# openSX70_ALADDIN_V398C-SEEED_20180222.net
KiCad netlist of a schematic drawn in EAGLE
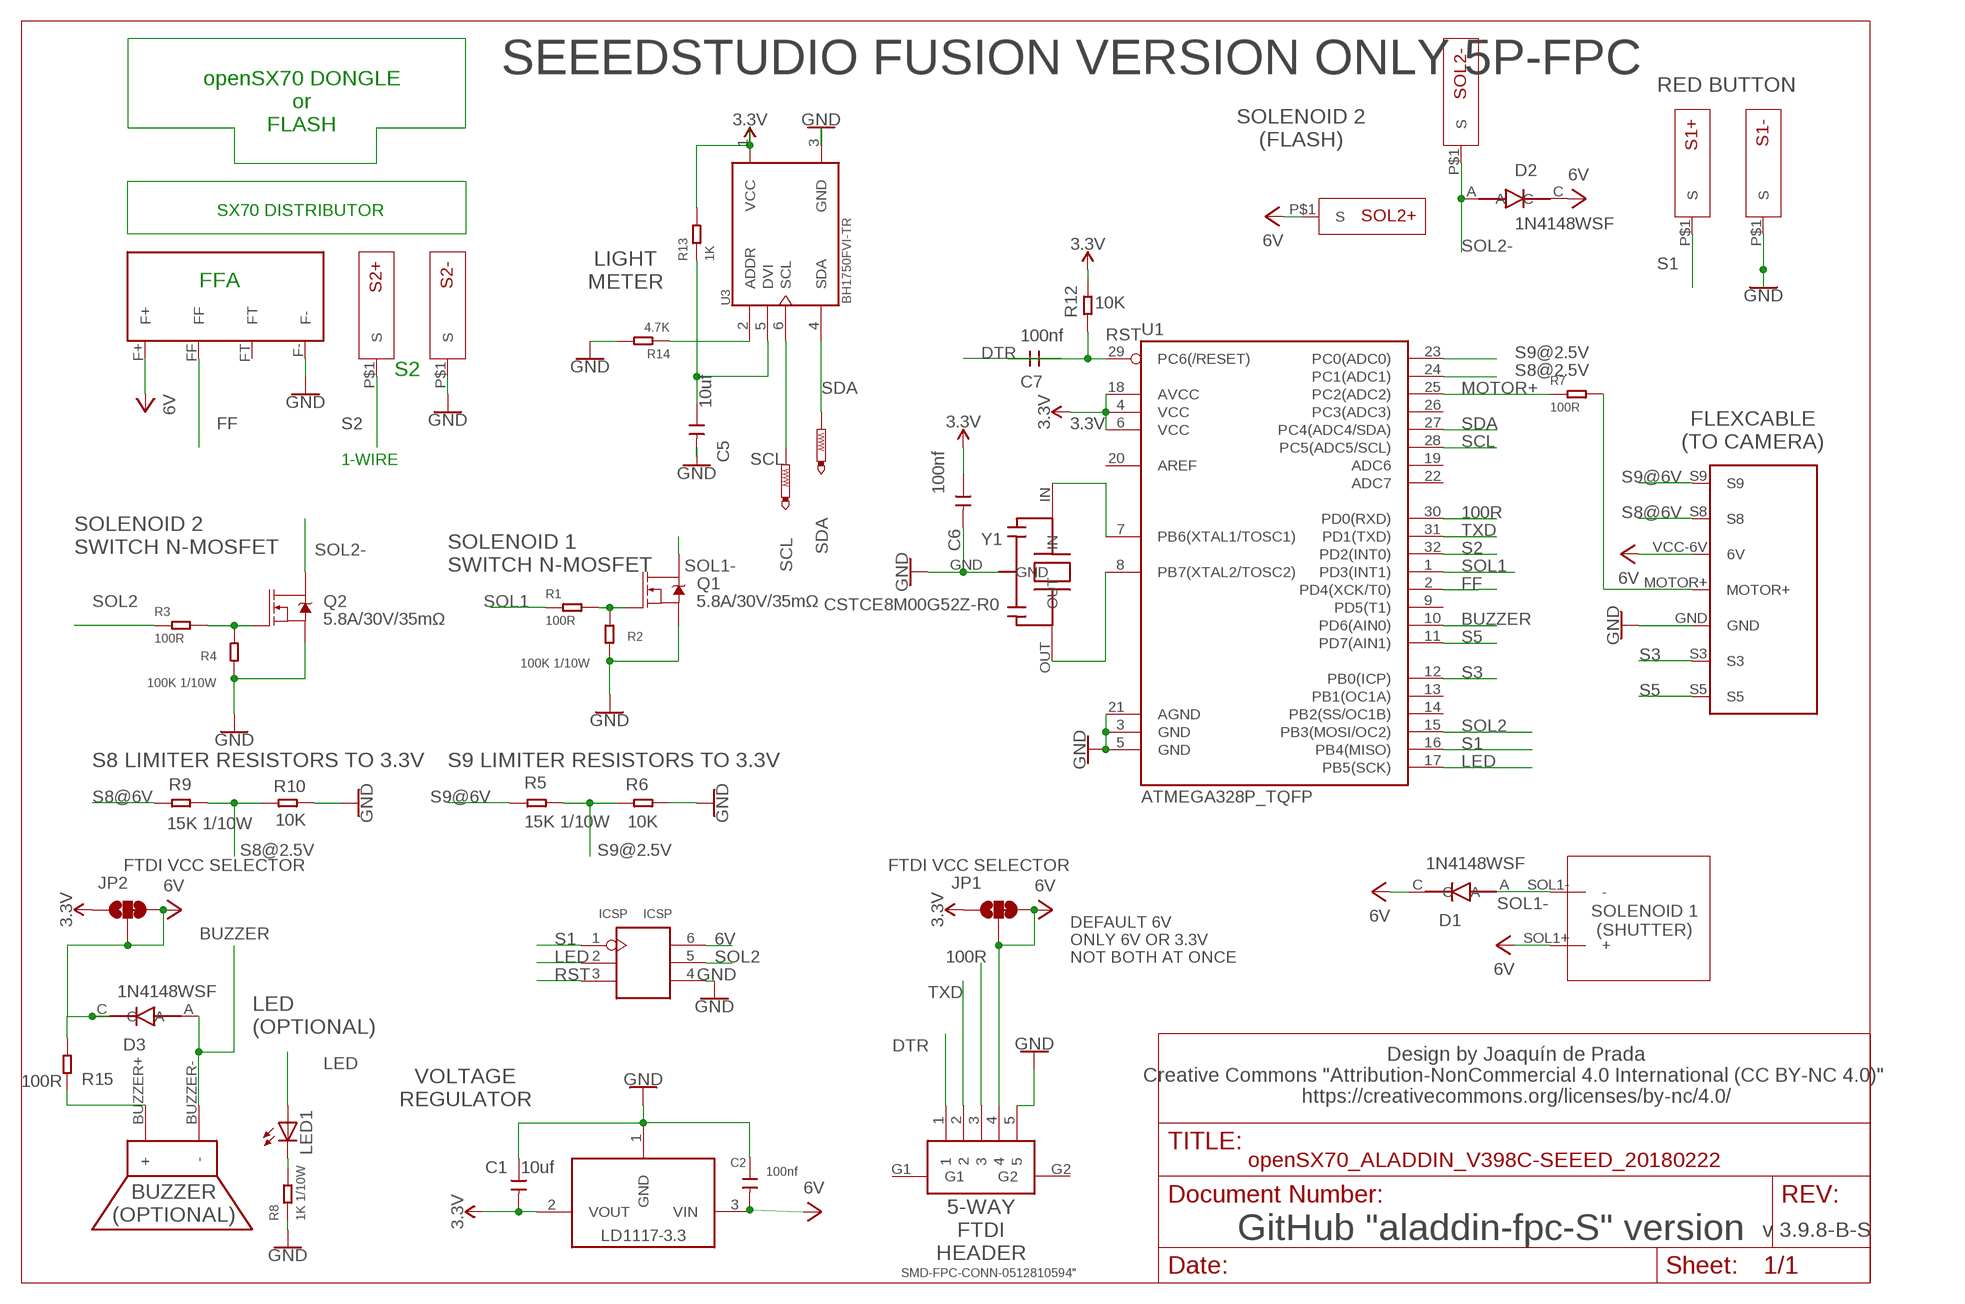
[diagram p0: schematic, sheet 1]

(export (version "E")
  (design (tool "Eeschema 10.0.6"))
  (components
    (comp (ref "C1")
      (value "10uf")
      (footprint "eagle-import:C0603")
      (fields (field (name "MPN") "CC0603KRX5R6BB106"))
      (libsource (lib "eagle-import") (part "CERAMIC-10UF-10V-10%-X5R(0603)"))
    )
    (comp (ref "C2")
      (value "100nf")
      (footprint "eagle-import:C0603")
      (fields (field (name "MPN") "CC0603KRX7R9BB104"))
      (libsource (lib "eagle-import") (part "CERAMIC-100NF-50V-10%-X7R(0603)"))
    )
    (comp (ref "C5")
      (value "10uf")
      (footprint "eagle-import:C0603")
      (fields (field (name "MPN") "CC0603KRX5R6BB106"))
      (libsource (lib "eagle-import") (part "CERAMIC-10UF-10V-10%-X5R(0603)"))
    )
    (comp (ref "C6")
      (value "100nf")
      (footprint "eagle-import:C0603")
      (fields (field (name "MPN") "CC0603KRX7R9BB104"))
      (libsource (lib "eagle-import") (part "CERAMIC-100NF-50V-10%-X7R(0603)"))
    )
    (comp (ref "C7")
      (value "100nf")
      (footprint "eagle-import:C0603")
      (fields (field (name "MPN") "CC0603KRX7R9BB104"))
      (libsource (lib "eagle-import") (part "CERAMIC-100NF-50V-10%-X7R(0603)"))
    )
    (comp (ref "D1")
      (value "1N4148WSF")
      (footprint "eagle-import:SODFL2512X100N")
      (fields (field (name "MANUFACTURER") "Fairchild Semiconductor"))
      (libsource (lib "eagle-import") (part "1N4148WS"))
    )
    (comp (ref "D2")
      (value "1N4148WSF")
      (footprint "eagle-import:SODFL2512X100N")
      (fields (field (name "MANUFACTURER") "Fairchild Semiconductor"))
      (libsource (lib "eagle-import") (part "1N4148WS"))
    )
    (comp (ref "D3")
      (value "1N4148WSF")
      (footprint "eagle-import:SODFL2512X100N")
      (fields (field (name "MANUFACTURER") "Fairchild Semiconductor"))
      (libsource (lib "eagle-import") (part "1N4148WS"))
    )
    (comp (ref "ICSP")
      (value "ICSP")
      (footprint "eagle-import:H2X3-2.54")
      (libsource (lib "eagle-import") (part "ICSP"))
    )
    (comp (ref "JP1")
      (value "FTDI VCC SELECTOR")
      (footprint "eagle-import:SMT-JUMPER_3_1-NC_TRACE_SILK")
      (libsource (lib "eagle-import") (part "JUMPER-SMT_3_1-NC_TRACE_SILK"))
    )
    (comp (ref "JP2")
      (value "FTDI VCC SELECTOR")
      (footprint "eagle-import:SMT-JUMPER_3_1-NC_TRACE_SILK")
      (libsource (lib "eagle-import") (part "JUMPER-SMT_3_1-NC_TRACE_SILK"))
    )
    (comp (ref "LD11172.5V")
      (value "LD1117 2.5V")
      (footprint "eagle-import:SOT223")
      (fields (field (name "MF") "Advanced Monolithic Systems") (field (name "MP") "AMS1117-5.0"))
      (libsource (lib "eagle-import") (part "LD1117-3.3"))
    )
    (comp (ref "LED1")
      (value "LEDCHIPLED_0805")
      (footprint "eagle-import:CHIPLED_0805")
      (libsource (lib "eagle-import") (part "LEDCHIPLED_0805"))
    )
    (comp (ref "Q1")
      (value "5.8A/30V/35mΩ")
      (footprint "eagle-import:SOT23-3")
      (libsource (lib "eagle-import") (part "MOSFET-NCH-AO3404A"))
    )
    (comp (ref "Q2")
      (value "5.8A/30V/35mΩ")
      (footprint "eagle-import:SOT23-3")
      (libsource (lib "eagle-import") (part "MOSFET-NCH-AO3404A"))
    )
    (comp (ref "R1")
      (value "100R")
      (footprint "eagle-import:R0603")
      (fields (field (name "MPN") "RC0603JR-07100RL"))
      (libsource (lib "eagle-import") (part "SMD-RES-100R-5%-1/10W(0603)"))
    )
    (comp (ref "R2")
      (value "100K 1/10W")
      (footprint "eagle-import:R0603")
      (fields (field (name "MPN") "RC0603JR-07100KL"))
      (libsource (lib "eagle-import") (part "SMD-RES-100K-5%-1/10W(0603)"))
    )
    (comp (ref "R3")
      (value "100R")
      (footprint "eagle-import:R0603")
      (fields (field (name "MPN") "RC0603JR-07100RL"))
      (libsource (lib "eagle-import") (part "SMD-RES-100R-5%-1/10W(0603)"))
    )
    (comp (ref "R4")
      (value "100K 1/10W")
      (footprint "eagle-import:R0603")
      (fields (field (name "MPN") "RC0603JR-07100KL"))
      (libsource (lib "eagle-import") (part "SMD-RES-100K-5%-1/10W(0603)"))
    )
    (comp (ref "R5")
      (value "15K 1/10W")
      (footprint "eagle-import:R0603")
      (fields (field (name "MPN") "RC0603FR-0715KL"))
      (libsource (lib "eagle-import") (part "SMD-RES-15K-1%-1/10W(0603)"))
    )
    (comp (ref "R6")
      (value "10K")
      (footprint "eagle-import:R0603")
      (fields (field (name "MPN") "RC0603FR-0710KL"))
      (libsource (lib "eagle-import") (part "SMD-RES-10K-1%-1/10W(0603)"))
    )
    (comp (ref "R7")
      (value "100R")
      (footprint "eagle-import:R0603")
      (fields (field (name "MPN") "RC0603JR-07100RL"))
      (libsource (lib "eagle-import") (part "SMD-RES-100R-5%-1/10W(0603)"))
    )
    (comp (ref "R8")
      (value "1K 1/10W")
      (footprint "eagle-import:R0603")
      (fields (field (name "MPN") "RC0603JR-071KL"))
      (libsource (lib "eagle-import") (part "SMD-RES-1K-5%-1/10W(0603)"))
    )
    (comp (ref "R9")
      (value "15K 1/10W")
      (footprint "eagle-import:R0603")
      (fields (field (name "MPN") "RC0603FR-0715KL"))
      (libsource (lib "eagle-import") (part "SMD-RES-15K-1%-1/10W(0603)"))
    )
    (comp (ref "R10")
      (value "10K")
      (footprint "eagle-import:R0603")
      (fields (field (name "MPN") "RC0603FR-0710KL"))
      (libsource (lib "eagle-import") (part "SMD-RES-10K-1%-1/10W(0603)"))
    )
    (comp (ref "R12")
      (value "10K")
      (footprint "eagle-import:R0603")
      (fields (field (name "MPN") "RC0603FR-0710KL"))
      (libsource (lib "eagle-import") (part "SMD-RES-10K-1%-1/10W(0603)"))
    )
    (comp (ref "R13")
      (value "1K")
      (footprint "eagle-import:R0603")
      (fields (field (name "MPN") "RC0603FR-071KL"))
      (libsource (lib "eagle-import") (part "SMD-RES-1K-1%-1/10W(0603)"))
    )
    (comp (ref "R14")
      (value "4.7K")
      (footprint "eagle-import:R0603")
      (fields (field (name "MPN") "RC0603JR-074K7L"))
      (libsource (lib "eagle-import") (part "SMD-RES-4.7K-5%-1/10W(0603)"))
    )
    (comp (ref "R15")
      (value "100R")
      (footprint "eagle-import:R0603")
      (fields (field (name "MPN") "RC0603JR-07100RL"))
      (libsource (lib "eagle-import") (part "SMD-RES-100R-5%-1/10W(0603)"))
    )
    (comp (ref "S1+")
      (value "SX70-S-PAD-NEW")
      (footprint "eagle-import:SX70-S-PAD2")
      (libsource (lib "eagle-import") (part "SX70-S-PAD-NEW"))
    )
    (comp (ref "S1-")
      (value "SX70-S-PAD-NEW")
      (footprint "eagle-import:SX70-S-PAD2")
      (libsource (lib "eagle-import") (part "SX70-S-PAD-NEW"))
    )
    (comp (ref "S2+")
      (value "SX70-S-PAD-NEW")
      (footprint "eagle-import:SX70-S-PAD2")
      (libsource (lib "eagle-import") (part "SX70-S-PAD-NEW"))
    )
    (comp (ref "S2-")
      (value "SX70-S-PAD-NEW")
      (footprint "eagle-import:SX70-S-PAD2")
      (libsource (lib "eagle-import") (part "SX70-S-PAD-NEW"))
    )
    (comp (ref "SCL")
      (value "PTR1TP08R")
      (footprint "eagle-import:TP08R")
      (libsource (lib "eagle-import") (part "PTR1TP08R"))
    )
    (comp (ref "SDA")
      (value "PTR1TP08R")
      (footprint "eagle-import:TP08R")
      (libsource (lib "eagle-import") (part "PTR1TP08R"))
    )
    (comp (ref "SOL1")
      (value "SX70-SOLENOID1-2PADS")
      (footprint "eagle-import:SX70-SOLENOID1-2")
      (libsource (lib "eagle-import") (part "SX70-SOLENOID1-2PADS"))
    )
    (comp (ref "SOL2+")
      (value "SX70-S-PAD-NEW")
      (footprint "eagle-import:SX70-S-PAD2")
      (libsource (lib "eagle-import") (part "SX70-S-PAD-NEW"))
    )
    (comp (ref "SOL2-")
      (value "SX70-S-PAD-NEW")
      (footprint "eagle-import:SX70-S-PAD2")
      (libsource (lib "eagle-import") (part "SX70-S-PAD-NEW"))
    )
    (comp (ref "U$1")
      (value "SX70-7-PAD")
      (footprint "eagle-import:SX70-7-PAD")
      (libsource (lib "eagle-import") (part "SX70-7-PAD"))
    )
    (comp (ref "U$2")
      (value "FFA")
      (footprint "eagle-import:FFA-PAD-PACKAGE")
      (libsource (lib "eagle-import") (part "SX70-FFA-PAD"))
    )
    (comp (ref "U$3")
      (value "CSET8-5G_V2")
      (footprint "eagle-import:CSET8-5G_PACKAGE")
      (libsource (lib "eagle-import") (part "CSET8-5G_V2"))
    )
    (comp (ref "U$4")
      (value "SMD-FPC-CONN-0512810594\"")
      (footprint "eagle-import:51281-0594")
      (libsource (lib "eagle-import") (part "SMD-FPC-CONN-0512810594{dblquote}"))
    )
    (comp (ref "U1")
      (value "ATMEGA328P_TQFP")
      (footprint "eagle-import:TQFP32-08")
      (libsource (lib "eagle-import") (part "ATMEGA328P_TQFP"))
    )
    (comp (ref "U3")
      (value "BH1750FVI-TR")
      (footprint "eagle-import:SOTFL50P300X75-6N")
      (fields (field (name "MF") "Rohm"))
      (libsource (lib "eagle-import") (part "BH1750FVI-TR"))
    )
    (comp (ref "Y1")
      (value "CSTCE8M00G52Z-R0")
      (footprint "eagle-import:CFP95P160X100-3N")
      (fields (field (name "MF") "Murata") (field (name "MP") "CSTCE16M0V53-R0"))
      (libsource (lib "eagle-import") (part "CSTCE16M0V53-R0"))
    )
  )
  (nets
    (net (code "1") (name "/100R") (class "Default")
      (node (ref "U$4") (pin "3") (pinfunction "3_3") (pintype "bidirectional"))
      (node (ref "U1") (pin "30") (pinfunction "PD0(RXD)_30") (pintype "bidirectional"))
    )
    (net (code "2") (name "/BUZZER") (class "Default")
      (node (ref "D3") (pin "A") (pinfunction "A_A") (pintype "passive"))
      (node (ref "U$3") (pin "BUZZER-") (pinfunction "-_BUZZER-") (pintype "bidirectional"))
      (node (ref "U1") (pin "10") (pinfunction "PD6(AIN0)_10") (pintype "bidirectional"))
    )
    (net (code "3") (name "/DTR") (class "Default")
      (node (ref "C7") (pin "1") (pinfunction "1_1") (pintype "passive"))
      (node (ref "U$4") (pin "1") (pinfunction "1_1") (pintype "bidirectional"))
    )
    (net (code "4") (name "/FF") (class "Default")
      (node (ref "U$2") (pin "FF") (pinfunction "FF_FF") (pintype "bidirectional"))
      (node (ref "U1") (pin "2") (pinfunction "PD4(XCK/T0)_2") (pintype "bidirectional"))
    )
    (net (code "5") (name "/LED") (class "Default")
      (node (ref "ICSP") (pin "2") (pinfunction "SCK_2") (pintype "bidirectional"))
      (node (ref "LED1") (pin "A") (pinfunction "A_A") (pintype "passive"))
      (node (ref "U1") (pin "17") (pinfunction "PB5(SCK)_17") (pintype "bidirectional"))
    )
    (net (code "6") (name "/MOTOR+") (class "Default")
      (node (ref "R7") (pin "1") (pinfunction "1_1") (pintype "passive"))
      (node (ref "U1") (pin "25") (pinfunction "PC2(ADC2)_25") (pintype "bidirectional"))
    )
    (net (code "7") (name "/RST") (class "Default")
      (node (ref "C7") (pin "2") (pinfunction "2_2") (pintype "passive"))
      (node (ref "ICSP") (pin "3") (pinfunction "RST_3") (pintype "bidirectional"))
      (node (ref "R12") (pin "1") (pinfunction "1_1") (pintype "passive"))
      (node (ref "U1") (pin "29") (pinfunction "PC6(/RESET)_29") (pintype "bidirectional"))
    )
    (net (code "8") (name "/S1") (class "Default")
      (node (ref "ICSP") (pin "1") (pinfunction "MISO_1") (pintype "bidirectional"))
      (node (ref "S1+") (pin "P$1") (pinfunction "S_P$1") (pintype "bidirectional"))
      (node (ref "U1") (pin "16") (pinfunction "PB4(MISO)_16") (pintype "bidirectional"))
    )
    (net (code "9") (name "/S2") (class "Default")
      (node (ref "S2+") (pin "P$1") (pinfunction "S_P$1") (pintype "bidirectional"))
      (node (ref "U1") (pin "32") (pinfunction "PD2(INT0)_32") (pintype "bidirectional"))
    )
    (net (code "10") (name "/S3") (class "Default")
      (node (ref "U$1") (pin "S3") (pinfunction "S3_S3") (pintype "bidirectional"))
      (node (ref "U1") (pin "12") (pinfunction "PB0(ICP)_12") (pintype "bidirectional"))
    )
    (net (code "11") (name "/S5") (class "Default")
      (node (ref "U$1") (pin "S5") (pinfunction "S5_S5") (pintype "bidirectional"))
      (node (ref "U1") (pin "11") (pinfunction "PD7(AIN1)_11") (pintype "bidirectional"))
    )
    (net (code "12") (name "/S8@2.5V") (class "Default")
      (node (ref "R10") (pin "1") (pinfunction "1_1") (pintype "passive"))
      (node (ref "R9") (pin "2") (pinfunction "2_2") (pintype "passive"))
      (node (ref "U1") (pin "24") (pinfunction "PC1(ADC1)_24") (pintype "bidirectional"))
    )
    (net (code "13") (name "/S8@6V") (class "Default")
      (node (ref "R9") (pin "1") (pinfunction "1_1") (pintype "passive"))
      (node (ref "U$1") (pin "S8") (pinfunction "S8_S8") (pintype "bidirectional"))
    )
    (net (code "14") (name "/S9@2.5V") (class "Default")
      (node (ref "R5") (pin "2") (pinfunction "2_2") (pintype "passive"))
      (node (ref "R6") (pin "1") (pinfunction "1_1") (pintype "passive"))
      (node (ref "U1") (pin "23") (pinfunction "PC0(ADC0)_23") (pintype "bidirectional"))
    )
    (net (code "15") (name "/S9@6V") (class "Default")
      (node (ref "R5") (pin "1") (pinfunction "1_1") (pintype "passive"))
      (node (ref "U$1") (pin "S9") (pinfunction "S9_S9") (pintype "bidirectional"))
    )
    (net (code "16") (name "/SCL") (class "Default")
      (node (ref "SCL") (pin "TP") (pinfunction "TP_TP") (pintype "input"))
      (node (ref "U1") (pin "28") (pinfunction "PC5(ADC5/SCL)_28") (pintype "bidirectional"))
      (node (ref "U3") (pin "6") (pinfunction "SCL_6") (pintype "input"))
    )
    (net (code "17") (name "/SDA") (class "Default")
      (node (ref "SDA") (pin "TP") (pinfunction "TP_TP") (pintype "input"))
      (node (ref "U1") (pin "27") (pinfunction "PC4(ADC4/SDA)_27") (pintype "bidirectional"))
      (node (ref "U3") (pin "4") (pinfunction "SDA_4") (pintype "bidirectional"))
    )
    (net (code "18") (name "/SOL1") (class "Default")
      (node (ref "R1") (pin "1") (pinfunction "1_1") (pintype "passive"))
      (node (ref "U1") (pin "1") (pinfunction "PD3(INT1)_1") (pintype "bidirectional"))
    )
    (net (code "19") (name "/SOL1-") (class "Default")
      (node (ref "D1") (pin "A") (pinfunction "A_A") (pintype "passive"))
      (node (ref "Q1") (pin "3") (pinfunction "D_3") (pintype "bidirectional"))
      (node (ref "SOL1") (pin "SOL1-") (pinfunction "-_SOL1-") (pintype "bidirectional"))
    )
    (net (code "20") (name "/SOL2") (class "Default")
      (node (ref "ICSP") (pin "5") (pinfunction "MOSI_5") (pintype "bidirectional"))
      (node (ref "R3") (pin "1") (pinfunction "1_1") (pintype "passive"))
      (node (ref "U1") (pin "15") (pinfunction "PB3(MOSI/OC2)_15") (pintype "bidirectional"))
    )
    (net (code "21") (name "/SOL2-") (class "Default")
      (node (ref "D2") (pin "A") (pinfunction "A_A") (pintype "passive"))
      (node (ref "Q2") (pin "3") (pinfunction "D_3") (pintype "bidirectional"))
      (node (ref "SOL2-") (pin "P$1") (pinfunction "S_P$1") (pintype "bidirectional"))
    )
    (net (code "22") (name "/TXD") (class "Default")
      (node (ref "U$4") (pin "2") (pinfunction "2_2") (pintype "bidirectional"))
      (node (ref "U1") (pin "31") (pinfunction "PD1(TXD)_31") (pintype "bidirectional"))
    )
    (net (code "23") (name "3.3V") (class "Default")
      (node (ref "C1") (pin "2") (pinfunction "2_2") (pintype "passive"))
      (node (ref "C6") (pin "1") (pinfunction "1_1") (pintype "passive"))
      (node (ref "JP1") (pin "1") (pinfunction "1_1") (pintype "passive"))
      (node (ref "JP2") (pin "1") (pinfunction "1_1") (pintype "passive"))
      (node (ref "LD11172.5V") (pin "2") (pinfunction "VOUT_2") (pintype "bidirectional"))
      (node (ref "R12") (pin "2") (pinfunction "2_2") (pintype "passive"))
      (node (ref "R13") (pin "2") (pinfunction "2_2") (pintype "passive"))
      (node (ref "U1") (pin "18") (pinfunction "AVCC_18") (pintype "bidirectional"))
      (node (ref "U1") (pin "4") (pinfunction "VCC_4") (pintype "bidirectional"))
      (node (ref "U1") (pin "6") (pinfunction "VCC_6") (pintype "bidirectional"))
      (node (ref "U3") (pin "1") (pinfunction "VCC_1") (pintype "power_in"))
    )
    (net (code "24") (name "6V") (class "Default")
      (node (ref "C2") (pin "2") (pinfunction "2_2") (pintype "passive"))
      (node (ref "D1") (pin "C") (pinfunction "C_C") (pintype "passive"))
      (node (ref "D2") (pin "C") (pinfunction "C_C") (pintype "passive"))
      (node (ref "D3") (pin "C") (pinfunction "C_C") (pintype "passive"))
      (node (ref "ICSP") (pin "6") (pinfunction "VCC_6") (pintype "bidirectional"))
      (node (ref "JP1") (pin "2") (pinfunction "2_2") (pintype "passive"))
      (node (ref "JP1") (pin "3") (pinfunction "3_3") (pintype "passive"))
      (node (ref "JP2") (pin "2") (pinfunction "2_2") (pintype "passive"))
      (node (ref "JP2") (pin "3") (pinfunction "3_3") (pintype "passive"))
      (node (ref "LD11172.5V") (pin "3") (pinfunction "VIN_3") (pintype "bidirectional"))
      (node (ref "R15") (pin "2") (pinfunction "2_2") (pintype "passive"))
      (node (ref "SOL1") (pin "SOL1+") (pinfunction "+_SOL1+") (pintype "bidirectional"))
      (node (ref "SOL2+") (pin "P$1") (pinfunction "S_P$1") (pintype "bidirectional"))
      (node (ref "U$1") (pin "VCC-6V") (pinfunction "6V_VCC-6V") (pintype "bidirectional"))
      (node (ref "U$2") (pin "F+") (pinfunction "F+_F+") (pintype "bidirectional"))
      (node (ref "U$4") (pin "4") (pinfunction "4_4") (pintype "bidirectional"))
    )
    (net (code "25") (name "GND") (class "Default")
      (node (ref "C1") (pin "1") (pinfunction "1_1") (pintype "passive"))
      (node (ref "C2") (pin "1") (pinfunction "1_1") (pintype "passive"))
      (node (ref "C5") (pin "2") (pinfunction "2_2") (pintype "passive"))
      (node (ref "C6") (pin "2") (pinfunction "2_2") (pintype "passive"))
      (node (ref "ICSP") (pin "4") (pinfunction "GND_4") (pintype "bidirectional"))
      (node (ref "LD11172.5V") (pin "1") (pinfunction "GND_1") (pintype "bidirectional"))
      (node (ref "Q1") (pin "2") (pinfunction "S_2") (pintype "bidirectional"))
      (node (ref "Q2") (pin "2") (pinfunction "S_2") (pintype "bidirectional"))
      (node (ref "R10") (pin "2") (pinfunction "2_2") (pintype "passive"))
      (node (ref "R14") (pin "2") (pinfunction "2_2") (pintype "passive"))
      (node (ref "R2") (pin "1") (pinfunction "1_1") (pintype "passive"))
      (node (ref "R4") (pin "1") (pinfunction "1_1") (pintype "passive"))
      (node (ref "R6") (pin "2") (pinfunction "2_2") (pintype "passive"))
      (node (ref "R8") (pin "1") (pinfunction "1_1") (pintype "passive"))
      (node (ref "S1-") (pin "P$1") (pinfunction "S_P$1") (pintype "bidirectional"))
      (node (ref "S2-") (pin "P$1") (pinfunction "S_P$1") (pintype "bidirectional"))
      (node (ref "U$1") (pin "GND") (pinfunction "GND_GND") (pintype "bidirectional"))
      (node (ref "U$2") (pin "F-") (pinfunction "F-_F-") (pintype "bidirectional"))
      (node (ref "U$4") (pin "5") (pinfunction "5_5") (pintype "bidirectional"))
      (node (ref "U1") (pin "21") (pinfunction "AGND_21") (pintype "bidirectional"))
      (node (ref "U1") (pin "3") (pinfunction "GND_3") (pintype "bidirectional"))
      (node (ref "U1") (pin "5") (pinfunction "GND_5") (pintype "bidirectional"))
      (node (ref "U3") (pin "3") (pinfunction "GND_3") (pintype "power_in"))
      (node (ref "Y1") (pin "GND") (pinfunction "GND_GND") (pintype "passive"))
    )
    (net (code "26") (name "Net-(LED1-PadC)") (class "Default")
      (node (ref "LED1") (pin "C") (pinfunction "C_C") (pintype "passive"))
      (node (ref "R8") (pin "2") (pinfunction "2_2") (pintype "passive"))
    )
    (net (code "27") (name "Net-(Q1-G)") (class "Default")
      (node (ref "Q1") (pin "1") (pinfunction "G_1") (pintype "bidirectional"))
      (node (ref "R1") (pin "2") (pinfunction "2_2") (pintype "passive"))
      (node (ref "R2") (pin "2") (pinfunction "2_2") (pintype "passive"))
    )
    (net (code "28") (name "Net-(Q2-G)") (class "Default")
      (node (ref "Q2") (pin "1") (pinfunction "G_1") (pintype "bidirectional"))
      (node (ref "R3") (pin "2") (pinfunction "2_2") (pintype "passive"))
      (node (ref "R4") (pin "2") (pinfunction "2_2") (pintype "passive"))
    )
    (net (code "29") (name "Net-(R7-Pad2)") (class "Default")
      (node (ref "R7") (pin "2") (pinfunction "2_2") (pintype "passive"))
      (node (ref "U$1") (pin "MOTOR+") (pinfunction "MOTOR+_MOTOR+") (pintype "bidirectional"))
    )
    (net (code "30") (name "Net-(U$3-+)") (class "Default")
      (node (ref "R15") (pin "1") (pinfunction "1_1") (pintype "passive"))
      (node (ref "U$3") (pin "BUZZER+") (pinfunction "+_BUZZER+") (pintype "bidirectional"))
    )
    (net (code "31") (name "Net-(U1-PB6(XTAL1{slash}TOSC1))") (class "Default")
      (node (ref "U1") (pin "7") (pinfunction "PB6(XTAL1/TOSC1)_7") (pintype "bidirectional"))
      (node (ref "Y1") (pin "IN") (pinfunction "IN_IN") (pintype "input"))
    )
    (net (code "32") (name "Net-(U1-PB7(XTAL2{slash}TOSC2))") (class "Default")
      (node (ref "U1") (pin "8") (pinfunction "PB7(XTAL2/TOSC2)_8") (pintype "bidirectional"))
      (node (ref "Y1") (pin "OUT") (pinfunction "OUT_OUT") (pintype "output"))
    )
    (net (code "33") (name "Net-(U3-ADDR)") (class "Default")
      (node (ref "R14") (pin "1") (pinfunction "1_1") (pintype "passive"))
      (node (ref "U3") (pin "2") (pinfunction "ADDR_2") (pintype "input"))
    )
    (net (code "34") (name "Net-(U3-DVI)") (class "Default")
      (node (ref "C5") (pin "1") (pinfunction "1_1") (pintype "passive"))
      (node (ref "R13") (pin "1") (pinfunction "1_1") (pintype "passive"))
      (node (ref "U3") (pin "5") (pinfunction "DVI_5") (pintype "input"))
    )
    (net (code "35") (name "unconnected-(U$2-PadFT)") (class "Default")
      (node (ref "U$2") (pin "FT") (pinfunction "FT_FT") (pintype "bidirectional"))
    )
    (net (code "36") (name "unconnected-(U$4-PadG1)") (class "Default")
      (node (ref "U$4") (pin "G1") (pinfunction "G1_G1") (pintype "bidirectional"))
    )
    (net (code "37") (name "unconnected-(U$4-PadG2)") (class "Default")
      (node (ref "U$4") (pin "G2") (pinfunction "G2_G2") (pintype "bidirectional"))
    )
    (net (code "38") (name "unconnected-(U1-ADC6-Pad19)") (class "Default")
      (node (ref "U1") (pin "19") (pinfunction "ADC6_19") (pintype "bidirectional"))
    )
    (net (code "39") (name "unconnected-(U1-ADC7-Pad22)") (class "Default")
      (node (ref "U1") (pin "22") (pinfunction "ADC7_22") (pintype "bidirectional"))
    )
    (net (code "40") (name "unconnected-(U1-AREF-Pad20)") (class "Default")
      (node (ref "U1") (pin "20") (pinfunction "AREF_20") (pintype "bidirectional"))
    )
    (net (code "41") (name "unconnected-(U1-PB1(OC1A)-Pad13)") (class "Default")
      (node (ref "U1") (pin "13") (pinfunction "PB1(OC1A)_13") (pintype "bidirectional"))
    )
    (net (code "42") (name "unconnected-(U1-PB2(SS{slash}OC1B)-Pad14)") (class "Default")
      (node (ref "U1") (pin "14") (pinfunction "PB2(SS/OC1B)_14") (pintype "bidirectional"))
    )
    (net (code "43") (name "unconnected-(U1-PC3(ADC3)-Pad26)") (class "Default")
      (node (ref "U1") (pin "26") (pinfunction "PC3(ADC3)_26") (pintype "bidirectional"))
    )
    (net (code "44") (name "unconnected-(U1-PD5(T1)-Pad9)") (class "Default")
      (node (ref "U1") (pin "9") (pinfunction "PD5(T1)_9") (pintype "bidirectional"))
    )
  )
)
